# one_sided_standalone_DWM1000.net
KiCad netlist of a schematic drawn in EAGLE
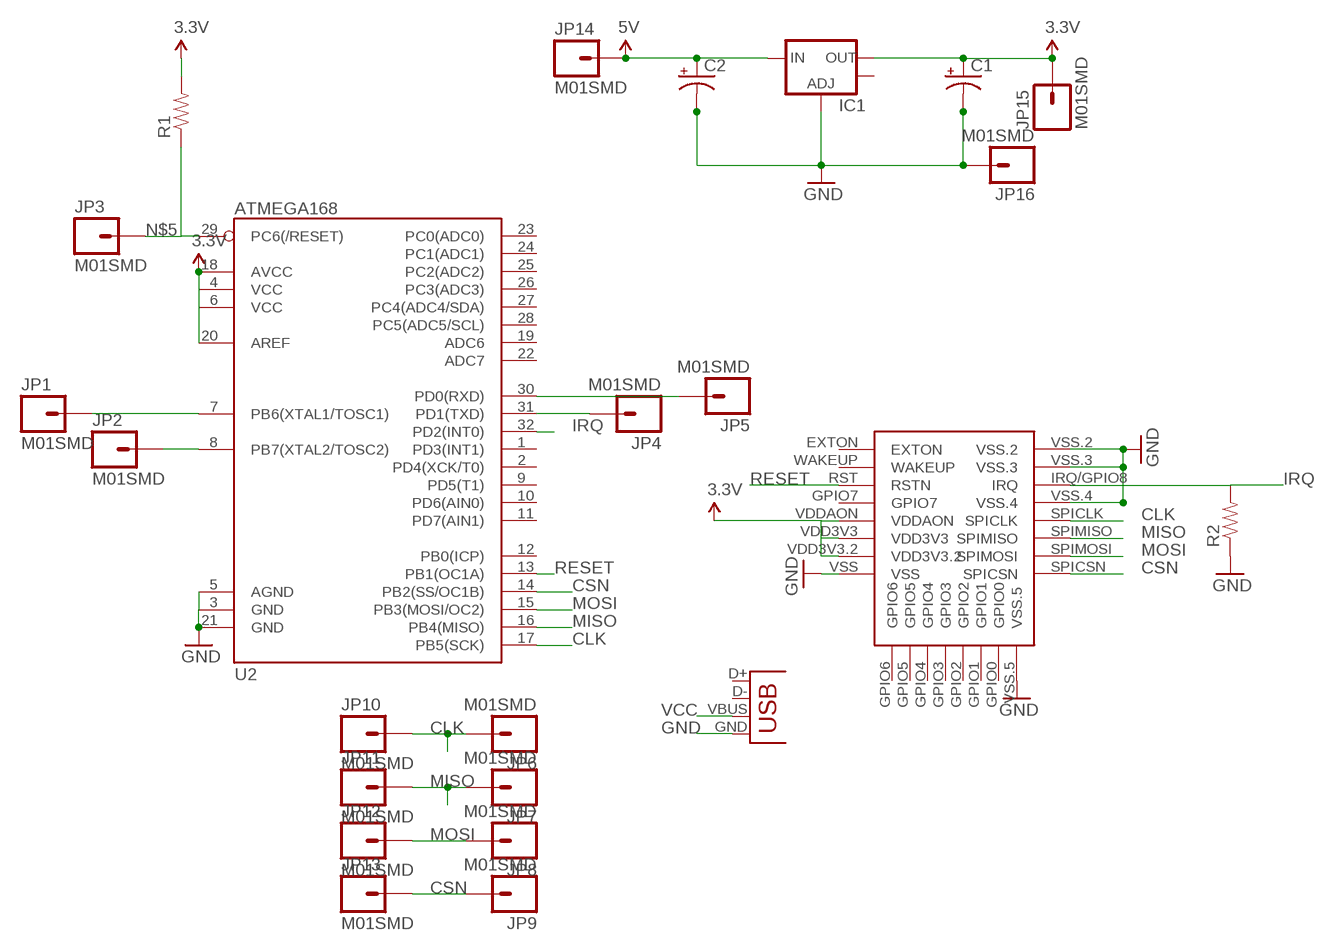
[diagram p0: schematic, sheet 1]

(export (version "E")
  (design (tool "Eeschema 10.0.6"))
  (components
    (comp (ref "C1")
      (value "CAP_POL3528-KIT")
      (footprint "eagle-import:EIA3528-KIT")
      (libsource (lib "eagle-import") (part "CAP_POL3528-KIT"))
    )
    (comp (ref "C2")
      (value "CAP_POL3528-KIT")
      (footprint "eagle-import:EIA3528-KIT")
      (libsource (lib "eagle-import") (part "CAP_POL3528-KIT"))
    )
    (comp (ref "IC1")
      (value "V_REG_LM1117SOT223")
      (footprint "eagle-import:SOT223")
      (libsource (lib "eagle-import") (part "V_REG_LM1117SOT223"))
    )
    (comp (ref "JP1")
      (value "M01SMD")
      (footprint "eagle-import:LUXEON-PAD")
      (libsource (lib "eagle-import") (part "M01SMD"))
    )
    (comp (ref "JP2")
      (value "M01SMD")
      (footprint "eagle-import:LUXEON-PAD")
      (libsource (lib "eagle-import") (part "M01SMD"))
    )
    (comp (ref "JP3")
      (value "M01SMD")
      (footprint "eagle-import:LUXEON-PAD")
      (libsource (lib "eagle-import") (part "M01SMD"))
    )
    (comp (ref "JP4")
      (value "M01SMD")
      (footprint "eagle-import:LUXEON-PAD")
      (libsource (lib "eagle-import") (part "M01SMD"))
    )
    (comp (ref "JP5")
      (value "M01SMD")
      (footprint "eagle-import:LUXEON-PAD")
      (libsource (lib "eagle-import") (part "M01SMD"))
    )
    (comp (ref "JP6")
      (value "M01SMD")
      (footprint "eagle-import:LUXEON-PAD")
      (libsource (lib "eagle-import") (part "M01SMD"))
    )
    (comp (ref "JP7")
      (value "M01SMD")
      (footprint "eagle-import:LUXEON-PAD")
      (libsource (lib "eagle-import") (part "M01SMD"))
    )
    (comp (ref "JP8")
      (value "M01SMD")
      (footprint "eagle-import:LUXEON-PAD")
      (libsource (lib "eagle-import") (part "M01SMD"))
    )
    (comp (ref "JP9")
      (value "M01SMD")
      (footprint "eagle-import:LUXEON-PAD")
      (libsource (lib "eagle-import") (part "M01SMD"))
    )
    (comp (ref "JP10")
      (value "M01SMD")
      (footprint "eagle-import:LUXEON-PAD")
      (libsource (lib "eagle-import") (part "M01SMD"))
    )
    (comp (ref "JP11")
      (value "M01SMD")
      (footprint "eagle-import:LUXEON-PAD")
      (libsource (lib "eagle-import") (part "M01SMD"))
    )
    (comp (ref "JP12")
      (value "M01SMD")
      (footprint "eagle-import:LUXEON-PAD")
      (libsource (lib "eagle-import") (part "M01SMD"))
    )
    (comp (ref "JP13")
      (value "M01SMD")
      (footprint "eagle-import:LUXEON-PAD")
      (libsource (lib "eagle-import") (part "M01SMD"))
    )
    (comp (ref "JP14")
      (value "M01SMD")
      (footprint "eagle-import:LUXEON-PAD")
      (libsource (lib "eagle-import") (part "M01SMD"))
    )
    (comp (ref "JP15")
      (value "M01SMD")
      (footprint "eagle-import:LUXEON-PAD")
      (libsource (lib "eagle-import") (part "M01SMD"))
    )
    (comp (ref "JP16")
      (value "M01SMD")
      (footprint "eagle-import:LUXEON-PAD")
      (libsource (lib "eagle-import") (part "M01SMD"))
    )
    (comp (ref "R1")
      (value "RESISTOR0805-RES")
      (footprint "eagle-import:0805")
      (libsource (lib "eagle-import") (part "RESISTOR0805-RES"))
    )
    (comp (ref "R2")
      (value "RESISTOR0805-RES")
      (footprint "eagle-import:0805")
      (libsource (lib "eagle-import") (part "RESISTOR0805-RES"))
    )
    (comp (ref "U$1")
      (value "DWM1000")
      (footprint "eagle-import:DWM1000")
      (libsource (lib "eagle-import") (part "DWM1000"))
    )
    (comp (ref "U2")
      (value "ATMEGA168")
      (footprint "eagle-import:TQFP32-08")
      (libsource (lib "eagle-import") (part "ATMEGA168"))
    )
    (comp (ref "X1")
      (value "USB-MICROB")
      (footprint "eagle-import:USB-MICROB")
      (libsource (lib "eagle-import") (part "USB-MICROB"))
    )
  )
  (nets
    (net (code "1") (name "/CLK") (class "Default")
      (node (ref "JP10") (pin "P$1") (pinfunction "1_P$1") (pintype "passive"))
      (node (ref "JP6") (pin "P$1") (pinfunction "1_P$1") (pintype "passive"))
      (node (ref "U$1") (pin "SPICLK") (pinfunction "SPICLK_SPICLK") (pintype "bidirectional"))
      (node (ref "U2") (pin "17") (pinfunction "PB5(SCK)_17") (pintype "bidirectional"))
    )
    (net (code "2") (name "/CSN") (class "Default")
      (node (ref "JP13") (pin "P$1") (pinfunction "1_P$1") (pintype "passive"))
      (node (ref "JP9") (pin "P$1") (pinfunction "1_P$1") (pintype "passive"))
      (node (ref "U$1") (pin "SPICSN") (pinfunction "SPICSN_SPICSN") (pintype "bidirectional"))
      (node (ref "U2") (pin "14") (pinfunction "PB2(SS/OC1B)_14") (pintype "bidirectional"))
    )
    (net (code "3") (name "/IRQ") (class "Default")
      (node (ref "R2") (pin "2") (pinfunction "2_2") (pintype "passive"))
      (node (ref "U$1") (pin "IRQ/GPIO8") (pinfunction "IRQ_IRQ/GPIO8") (pintype "bidirectional"))
      (node (ref "U2") (pin "32") (pinfunction "PD2(INT0)_32") (pintype "bidirectional"))
    )
    (net (code "4") (name "/MISO") (class "Default")
      (node (ref "JP11") (pin "P$1") (pinfunction "1_P$1") (pintype "passive"))
      (node (ref "JP7") (pin "P$1") (pinfunction "1_P$1") (pintype "passive"))
      (node (ref "U$1") (pin "SPIMISO") (pinfunction "SPIMISO_SPIMISO") (pintype "bidirectional"))
      (node (ref "U2") (pin "16") (pinfunction "PB4(MISO)_16") (pintype "bidirectional"))
    )
    (net (code "5") (name "/MOSI") (class "Default")
      (node (ref "JP12") (pin "P$1") (pinfunction "1_P$1") (pintype "passive"))
      (node (ref "JP8") (pin "P$1") (pinfunction "1_P$1") (pintype "passive"))
      (node (ref "U$1") (pin "SPIMOSI") (pinfunction "SPIMOSI_SPIMOSI") (pintype "bidirectional"))
      (node (ref "U2") (pin "15") (pinfunction "PB3(MOSI/OC2)_15") (pintype "bidirectional"))
    )
    (net (code "6") (name "/N$5") (class "Default")
      (node (ref "JP3") (pin "P$1") (pinfunction "1_P$1") (pintype "passive"))
      (node (ref "R1") (pin "1") (pinfunction "1_1") (pintype "passive"))
      (node (ref "U2") (pin "29") (pinfunction "PC6(/RESET)_29") (pintype "bidirectional"))
    )
    (net (code "7") (name "/RESET") (class "Default")
      (node (ref "U$1") (pin "RST") (pinfunction "RSTN_RST") (pintype "bidirectional"))
      (node (ref "U2") (pin "13") (pinfunction "PB1(OC1A)_13") (pintype "bidirectional"))
    )
    (net (code "8") (name "3.3V") (class "Default")
      (node (ref "C1") (pin "A") (pinfunction "+_A") (pintype "passive"))
      (node (ref "IC1") (pin "2") (pinfunction "OUT_2") (pintype "output"))
      (node (ref "JP15") (pin "P$1") (pinfunction "1_P$1") (pintype "passive"))
      (node (ref "R1") (pin "2") (pinfunction "2_2") (pintype "passive"))
      (node (ref "U$1") (pin "VDD3V3") (pinfunction "VDD3V3_VDD3V3") (pintype "bidirectional"))
      (node (ref "U$1") (pin "VDD3V3.2") (pinfunction "VDD3V3.2_VDD3V3.2") (pintype "bidirectional"))
      (node (ref "U$1") (pin "VDDAON") (pinfunction "VDDAON_VDDAON") (pintype "bidirectional"))
      (node (ref "U2") (pin "18") (pinfunction "AVCC_18") (pintype "bidirectional"))
      (node (ref "U2") (pin "20") (pinfunction "AREF_20") (pintype "bidirectional"))
      (node (ref "U2") (pin "6") (pinfunction "VCC_6") (pintype "bidirectional"))
    )
    (net (code "9") (name "5V") (class "Default")
      (node (ref "C2") (pin "A") (pinfunction "+_A") (pintype "passive"))
      (node (ref "IC1") (pin "3") (pinfunction "IN_3") (pintype "input"))
      (node (ref "JP14") (pin "P$1") (pinfunction "1_P$1") (pintype "passive"))
      (node (ref "X1") (pin "VBUS") (pinfunction "VBUS_VBUS") (pintype "bidirectional"))
    )
    (net (code "10") (name "GND") (class "Default")
      (node (ref "C1") (pin "C") (pinfunction "-_C") (pintype "passive"))
      (node (ref "C2") (pin "C") (pinfunction "-_C") (pintype "passive"))
      (node (ref "IC1") (pin "1") (pinfunction "ADJ_1") (pintype "input"))
      (node (ref "JP16") (pin "P$1") (pinfunction "1_P$1") (pintype "passive"))
      (node (ref "R2") (pin "1") (pinfunction "1_1") (pintype "passive"))
      (node (ref "U$1") (pin "VSS") (pinfunction "VSS_VSS") (pintype "bidirectional"))
      (node (ref "U$1") (pin "VSS.2") (pinfunction "VSS.2_VSS.2") (pintype "bidirectional"))
      (node (ref "U$1") (pin "VSS.3") (pinfunction "VSS.3_VSS.3") (pintype "bidirectional"))
      (node (ref "U$1") (pin "VSS.4") (pinfunction "VSS.4_VSS.4") (pintype "bidirectional"))
      (node (ref "U$1") (pin "VSS.5") (pinfunction "VSS.5_VSS.5") (pintype "bidirectional"))
      (node (ref "U2") (pin "21") (pinfunction "GND_21") (pintype "bidirectional"))
      (node (ref "U2") (pin "3") (pinfunction "GND_3") (pintype "bidirectional"))
      (node (ref "U2") (pin "5") (pinfunction "AGND_5") (pintype "bidirectional"))
      (node (ref "X1") (pin "GND") (pinfunction "GND_GND") (pintype "bidirectional"))
    )
    (net (code "11") (name "Net-(JP1-1)") (class "Default")
      (node (ref "JP1") (pin "P$1") (pinfunction "1_P$1") (pintype "passive"))
      (node (ref "U2") (pin "7") (pinfunction "PB6(XTAL1/TOSC1)_7") (pintype "bidirectional"))
    )
    (net (code "12") (name "Net-(JP2-1)") (class "Default")
      (node (ref "JP2") (pin "P$1") (pinfunction "1_P$1") (pintype "passive"))
      (node (ref "U2") (pin "8") (pinfunction "PB7(XTAL2/TOSC2)_8") (pintype "bidirectional"))
    )
    (net (code "13") (name "Net-(JP4-1)") (class "Default")
      (node (ref "JP4") (pin "P$1") (pinfunction "1_P$1") (pintype "passive"))
      (node (ref "U2") (pin "31") (pinfunction "PD1(TXD)_31") (pintype "bidirectional"))
    )
    (net (code "14") (name "Net-(JP5-1)") (class "Default")
      (node (ref "JP5") (pin "P$1") (pinfunction "1_P$1") (pintype "passive"))
      (node (ref "U2") (pin "30") (pinfunction "PD0(RXD)_30") (pintype "bidirectional"))
    )
    (net (code "15") (name "unconnected-(IC1-OUT-Pad4)") (class "Default")
      (node (ref "IC1") (pin "4") (pinfunction "OUT_4") (pintype "output"))
    )
    (net (code "16") (name "unconnected-(U$1-PadEXTON)") (class "Default")
      (node (ref "U$1") (pin "EXTON") (pinfunction "EXTON_EXTON") (pintype "bidirectional"))
    )
    (net (code "17") (name "unconnected-(U$1-PadGPIO0)") (class "Default")
      (node (ref "U$1") (pin "GPIO0") (pinfunction "GPIO0_GPIO0") (pintype "bidirectional"))
    )
    (net (code "18") (name "unconnected-(U$1-PadGPIO1)") (class "Default")
      (node (ref "U$1") (pin "GPIO1") (pinfunction "GPIO1_GPIO1") (pintype "bidirectional"))
    )
    (net (code "19") (name "unconnected-(U$1-PadGPIO2)") (class "Default")
      (node (ref "U$1") (pin "GPIO2") (pinfunction "GPIO2_GPIO2") (pintype "bidirectional"))
    )
    (net (code "20") (name "unconnected-(U$1-PadGPIO3)") (class "Default")
      (node (ref "U$1") (pin "GPIO3") (pinfunction "GPIO3_GPIO3") (pintype "bidirectional"))
    )
    (net (code "21") (name "unconnected-(U$1-PadGPIO4)") (class "Default")
      (node (ref "U$1") (pin "GPIO4") (pinfunction "GPIO4_GPIO4") (pintype "bidirectional"))
    )
    (net (code "22") (name "unconnected-(U$1-PadGPIO5)") (class "Default")
      (node (ref "U$1") (pin "GPIO5") (pinfunction "GPIO5_GPIO5") (pintype "bidirectional"))
    )
    (net (code "23") (name "unconnected-(U$1-PadGPIO6)") (class "Default")
      (node (ref "U$1") (pin "GPIO6") (pinfunction "GPIO6_GPIO6") (pintype "bidirectional"))
    )
    (net (code "24") (name "unconnected-(U$1-PadGPIO7)") (class "Default")
      (node (ref "U$1") (pin "GPIO7") (pinfunction "GPIO7_GPIO7") (pintype "bidirectional"))
    )
    (net (code "25") (name "unconnected-(U$1-PadWAKEUP)") (class "Default")
      (node (ref "U$1") (pin "WAKEUP") (pinfunction "WAKEUP_WAKEUP") (pintype "bidirectional"))
    )
    (net (code "26") (name "unconnected-(U2-ADC6-Pad19)") (class "Default")
      (node (ref "U2") (pin "19") (pinfunction "ADC6_19") (pintype "bidirectional"))
    )
    (net (code "27") (name "unconnected-(U2-ADC7-Pad22)") (class "Default")
      (node (ref "U2") (pin "22") (pinfunction "ADC7_22") (pintype "bidirectional"))
    )
    (net (code "28") (name "unconnected-(U2-PB0(ICP)-Pad12)") (class "Default")
      (node (ref "U2") (pin "12") (pinfunction "PB0(ICP)_12") (pintype "bidirectional"))
    )
    (net (code "29") (name "unconnected-(U2-PC0(ADC0)-Pad23)") (class "Default")
      (node (ref "U2") (pin "23") (pinfunction "PC0(ADC0)_23") (pintype "bidirectional"))
    )
    (net (code "30") (name "unconnected-(U2-PC1(ADC1)-Pad24)") (class "Default")
      (node (ref "U2") (pin "24") (pinfunction "PC1(ADC1)_24") (pintype "bidirectional"))
    )
    (net (code "31") (name "unconnected-(U2-PC2(ADC2)-Pad25)") (class "Default")
      (node (ref "U2") (pin "25") (pinfunction "PC2(ADC2)_25") (pintype "bidirectional"))
    )
    (net (code "32") (name "unconnected-(U2-PC3(ADC3)-Pad26)") (class "Default")
      (node (ref "U2") (pin "26") (pinfunction "PC3(ADC3)_26") (pintype "bidirectional"))
    )
    (net (code "33") (name "unconnected-(U2-PC4(ADC4{slash}SDA)-Pad27)") (class "Default")
      (node (ref "U2") (pin "27") (pinfunction "PC4(ADC4/SDA)_27") (pintype "bidirectional"))
    )
    (net (code "34") (name "unconnected-(U2-PC5(ADC5{slash}SCL)-Pad28)") (class "Default")
      (node (ref "U2") (pin "28") (pinfunction "PC5(ADC5/SCL)_28") (pintype "bidirectional"))
    )
    (net (code "35") (name "unconnected-(U2-PD3(INT1)-Pad1)") (class "Default")
      (node (ref "U2") (pin "1") (pinfunction "PD3(INT1)_1") (pintype "bidirectional"))
    )
    (net (code "36") (name "unconnected-(U2-PD4(XCK{slash}T0)-Pad2)") (class "Default")
      (node (ref "U2") (pin "2") (pinfunction "PD4(XCK/T0)_2") (pintype "bidirectional"))
    )
    (net (code "37") (name "unconnected-(U2-PD5(T1)-Pad9)") (class "Default")
      (node (ref "U2") (pin "9") (pinfunction "PD5(T1)_9") (pintype "bidirectional"))
    )
    (net (code "38") (name "unconnected-(U2-PD6(AIN0)-Pad10)") (class "Default")
      (node (ref "U2") (pin "10") (pinfunction "PD6(AIN0)_10") (pintype "bidirectional"))
    )
    (net (code "39") (name "unconnected-(U2-PD7(AIN1)-Pad11)") (class "Default")
      (node (ref "U2") (pin "11") (pinfunction "PD7(AIN1)_11") (pintype "bidirectional"))
    )
    (net (code "40") (name "unconnected-(U2-VCC-Pad4)") (class "Default")
      (node (ref "U2") (pin "4") (pinfunction "VCC_4") (pintype "bidirectional"))
    )
    (net (code "41") (name "unconnected-(X1-PadD+)") (class "Default")
      (node (ref "X1") (pin "D+") (pinfunction "D+_D+") (pintype "bidirectional"))
    )
    (net (code "42") (name "unconnected-(X1-PadD-)") (class "Default")
      (node (ref "X1") (pin "D-") (pinfunction "D-_D-") (pintype "bidirectional"))
    )
  )
)
